# main_board.net
KiCad netlist of a schematic drawn in EAGLE
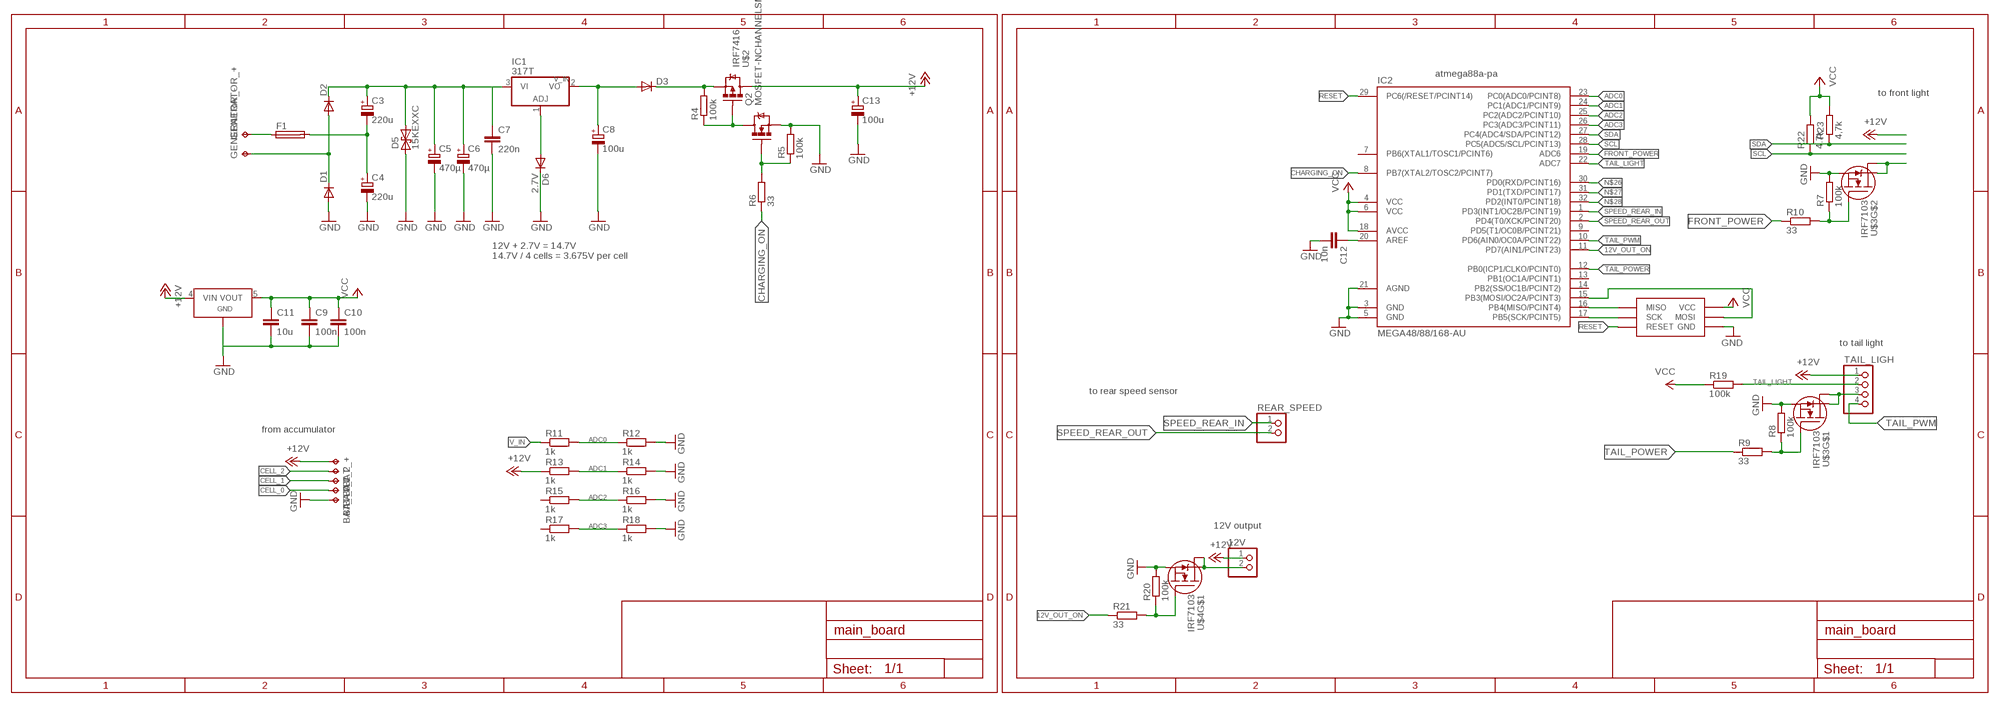
[diagram p0: schematic, sheet 1]

(export (version "E")
  (design (tool "Eeschema 10.0.6"))
  (components
    (comp (ref "12V")
      (value "PINHD-1X2")
      (footprint "eagle-import:1X02")
      (libsource (lib "eagle-import") (part "PINHD-1X2"))
    )
    (comp (ref "BAT_+")
      (value "TPTP18SQ")
      (footprint "eagle-import:TP18SQ")
      (libsource (lib "eagle-import") (part "TPTP18SQ"))
    )
    (comp (ref "BAT_-")
      (value "TPTP18SQ")
      (footprint "eagle-import:TP18SQ")
      (libsource (lib "eagle-import") (part "TPTP18SQ"))
    )
    (comp (ref "BAT_0")
      (value "TPTP18SQ")
      (footprint "eagle-import:TP18SQ")
      (libsource (lib "eagle-import") (part "TPTP18SQ"))
    )
    (comp (ref "BAT_1")
      (value "TPTP18SQ")
      (footprint "eagle-import:TP18SQ")
      (libsource (lib "eagle-import") (part "TPTP18SQ"))
    )
    (comp (ref "BAT_2")
      (value "TPTP18SQ")
      (footprint "eagle-import:TP18SQ")
      (libsource (lib "eagle-import") (part "TPTP18SQ"))
    )
    (comp (ref "C3")
      (value "220u")
      (footprint "eagle-import:PANASONIC_F")
      (libsource (lib "eagle-import") (part "CPOL-EUF"))
    )
    (comp (ref "C4")
      (value "220u")
      (footprint "eagle-import:PANASONIC_F")
      (libsource (lib "eagle-import") (part "CPOL-EUF"))
    )
    (comp (ref "C5")
      (value "470µ")
      (footprint "eagle-import:153CLV-1014")
      (libsource (lib "eagle-import") (part "CPOL-EU153CLV-1014"))
    )
    (comp (ref "C6")
      (value "470µ")
      (footprint "eagle-import:153CLV-1014")
      (libsource (lib "eagle-import") (part "CPOL-EU153CLV-1014"))
    )
    (comp (ref "C7")
      (value "220n")
      (footprint "eagle-import:C0805")
      (libsource (lib "eagle-import") (part "C-EUC0805"))
    )
    (comp (ref "C8")
      (value "100u")
      (footprint "eagle-import:PANASONIC_E")
      (libsource (lib "eagle-import") (part "CPOL-EUE"))
    )
    (comp (ref "C9")
      (value "100n")
      (footprint "eagle-import:C0805")
      (libsource (lib "eagle-import") (part "C-EUC0805"))
    )
    (comp (ref "C10")
      (value "100n")
      (footprint "eagle-import:C0805")
      (libsource (lib "eagle-import") (part "C-EUC0805"))
    )
    (comp (ref "C11")
      (value "10u")
      (footprint "eagle-import:C1206")
      (libsource (lib "eagle-import") (part "C-EUC1206"))
    )
    (comp (ref "C12")
      (value "10n")
      (footprint "eagle-import:C0805")
      (libsource (lib "eagle-import") (part "C-EUC0805"))
    )
    (comp (ref "C13")
      (value "100u")
      (footprint "eagle-import:PANASONIC_E")
      (libsource (lib "eagle-import") (part "CPOL-EUE"))
    )
    (comp (ref "D1")
      (value "DIODE-DO-214AC")
      (footprint "eagle-import:DO-214AC")
      (libsource (lib "eagle-import") (part "DIODE-DO-214AC"))
    )
    (comp (ref "D2")
      (value "DIODE-DO-214AC")
      (footprint "eagle-import:DO-214AC")
      (libsource (lib "eagle-import") (part "DIODE-DO-214AC"))
    )
    (comp (ref "D3")
      (value "DIODE-DO-214AC")
      (footprint "eagle-import:DO-214AC")
      (libsource (lib "eagle-import") (part "DIODE-DO-214AC"))
    )
    (comp (ref "D5")
      (value "15KEXXC")
      (footprint "eagle-import:CB429-17")
      (libsource (lib "eagle-import") (part "15KEXXC"))
    )
    (comp (ref "D6")
      (value "2.7V")
      (footprint "eagle-import:MINIMELF")
      (libsource (lib "eagle-import") (part "DIODE-MINIMELF"))
    )
    (comp (ref "F1")
      (value "TE5")
      (footprint "eagle-import:TE5")
      (fields (field (name "OC_FARNELL") "unknown") (field (name "OC_NEWARK") "unknown"))
      (libsource (lib "eagle-import") (part "TE5"))
    )
    (comp (ref "GENERATOR_+")
      (value "TPTP18SQ")
      (footprint "eagle-import:TP18SQ")
      (libsource (lib "eagle-import") (part "TPTP18SQ"))
    )
    (comp (ref "GENERATOR_-")
      (value "TPTP18SQ")
      (footprint "eagle-import:TP18SQ")
      (libsource (lib "eagle-import") (part "TPTP18SQ"))
    )
    (comp (ref "IC1")
      (value "317T")
      (footprint "eagle-import:TO220H")
      (libsource (lib "eagle-import") (part "317T"))
    )
    (comp (ref "IC2")
      (value "MEGA48/88/168-AU")
      (footprint "eagle-import:TQFP32-08")
      (libsource (lib "eagle-import") (part "MEGA48/88/168-AU"))
    )
    (comp (ref "Q2")
      (value "MOSFET-NCHANNELSMD")
      (footprint "eagle-import:SOT23-3")
      (libsource (lib "eagle-import") (part "MOSFET-NCHANNELSMD"))
    )
    (comp (ref "R4")
      (value "100k")
      (footprint "eagle-import:R0603")
      (libsource (lib "eagle-import") (part "R-EU_R0603"))
    )
    (comp (ref "R5")
      (value "100k")
      (footprint "eagle-import:R0603")
      (libsource (lib "eagle-import") (part "R-EU_R0603"))
    )
    (comp (ref "R6")
      (value "33")
      (footprint "eagle-import:R0603")
      (libsource (lib "eagle-import") (part "R-EU_R0603"))
    )
    (comp (ref "R7")
      (value "100k")
      (footprint "eagle-import:R0603")
      (libsource (lib "eagle-import") (part "R-EU_R0603"))
    )
    (comp (ref "R8")
      (value "100k")
      (footprint "eagle-import:R0603")
      (libsource (lib "eagle-import") (part "R-EU_R0603"))
    )
    (comp (ref "R9")
      (value "33")
      (footprint "eagle-import:R0603")
      (libsource (lib "eagle-import") (part "R-EU_R0603"))
    )
    (comp (ref "R10")
      (value "33")
      (footprint "eagle-import:R0603")
      (libsource (lib "eagle-import") (part "R-EU_R0603"))
    )
    (comp (ref "R11")
      (value "1k")
      (footprint "eagle-import:R0603")
      (libsource (lib "eagle-import") (part "R-EU_R0603"))
    )
    (comp (ref "R12")
      (value "1k")
      (footprint "eagle-import:R0603")
      (libsource (lib "eagle-import") (part "R-EU_R0603"))
    )
    (comp (ref "R13")
      (value "1k")
      (footprint "eagle-import:R0603")
      (libsource (lib "eagle-import") (part "R-EU_R0603"))
    )
    (comp (ref "R14")
      (value "1k")
      (footprint "eagle-import:R0603")
      (libsource (lib "eagle-import") (part "R-EU_R0603"))
    )
    (comp (ref "R15")
      (value "1k")
      (footprint "eagle-import:R0603")
      (libsource (lib "eagle-import") (part "R-EU_R0603"))
    )
    (comp (ref "R16")
      (value "1k")
      (footprint "eagle-import:R0603")
      (libsource (lib "eagle-import") (part "R-EU_R0603"))
    )
    (comp (ref "R17")
      (value "1k")
      (footprint "eagle-import:R0603")
      (libsource (lib "eagle-import") (part "R-EU_R0603"))
    )
    (comp (ref "R18")
      (value "1k")
      (footprint "eagle-import:R0603")
      (libsource (lib "eagle-import") (part "R-EU_R0603"))
    )
    (comp (ref "R19")
      (value "100k")
      (footprint "eagle-import:R0603")
      (libsource (lib "eagle-import") (part "R-EU_R0603"))
    )
    (comp (ref "R20")
      (value "100k")
      (footprint "eagle-import:R0603")
      (libsource (lib "eagle-import") (part "R-EU_R0603"))
    )
    (comp (ref "R21")
      (value "33")
      (footprint "eagle-import:R0603")
      (libsource (lib "eagle-import") (part "R-EU_R0603"))
    )
    (comp (ref "R22")
      (value "4.7k")
      (footprint "eagle-import:R0603")
      (libsource (lib "eagle-import") (part "R-EU_R0603"))
    )
    (comp (ref "R23")
      (value "4,7k")
      (footprint "eagle-import:R0603")
      (libsource (lib "eagle-import") (part "R-EU_R0603"))
    )
    (comp (ref "REAR_SPEED")
      (value "PINHD-1X2")
      (footprint "eagle-import:1X02")
      (libsource (lib "eagle-import") (part "PINHD-1X2"))
    )
    (comp (ref "TAIL_LIGH")
      (value "PINHD-1X4")
      (footprint "eagle-import:1X04")
      (libsource (lib "eagle-import") (part "PINHD-1X4"))
    )
    (comp (ref "U$1")
      (value "TPS71530")
      (footprint "eagle-import:SOT23-DBV")
      (libsource (lib "eagle-import") (part "TPS71530"))
    )
    (comp (ref "U$2")
      (value "IRF7416")
      (footprint "eagle-import:SO8-2")
      (libsource (lib "eagle-import") (part "IRF7416"))
    )
    (comp (ref "U$3")
      (value "IRF7103")
      (footprint "eagle-import:SO8-2")
      (libsource (lib "eagle-import") (part "IRF7103"))
    )
    (comp (ref "U$4")
      (value "IRF7103")
      (footprint "eagle-import:SO8-2")
      (libsource (lib "eagle-import") (part "IRF7103"))
    )
    (comp (ref "U$5")
      (value "ISP_SPECIALS")
      (footprint "eagle-import:ISP_RM2_00_STRAIGHT")
      (libsource (lib "eagle-import") (part "ISP_SPECIALS"))
    )
  )
  (nets
    (net (code "1") (name "+12V") (class "Default")
      (node (ref "12V") (pin "1") (pinfunction "1_1") (pintype "passive"))
      (node (ref "BAT_+") (pin "TP") (pinfunction "TP_TP") (pintype "input"))
      (node (ref "C13") (pin "+") (pinfunction "+_+") (pintype "passive"))
      (node (ref "R13") (pin "1") (pinfunction "1_1") (pintype "passive"))
      (node (ref "TAIL_LIGH") (pin "1") (pinfunction "1_1") (pintype "passive"))
      (node (ref "U$1") (pin "4") (pinfunction "VIN_4") (pintype "power_in"))
      (node (ref "U$2") (pin "5") (pinfunction "D1_5") (pintype "passive"))
      (node (ref "U$2") (pin "6") (pinfunction "D1_6") (pintype "passive"))
      (node (ref "U$2") (pin "7") (pinfunction "D1_7") (pintype "passive"))
      (node (ref "U$2") (pin "8") (pinfunction "D1_8") (pintype "passive"))
    )
    (net (code "2") (name "12V_OUT_ON") (class "Default")
      (node (ref "IC2") (pin "11") (pinfunction "PD7(AIN1/PCINT23)_11") (pintype "bidirectional"))
      (node (ref "R21") (pin "1") (pinfunction "1_1") (pintype "passive"))
    )
    (net (code "3") (name "ADC0") (class "Default")
      (node (ref "IC2") (pin "23") (pinfunction "PC0(ADC0/PCINT8)_23") (pintype "bidirectional"))
      (node (ref "R11") (pin "2") (pinfunction "2_2") (pintype "passive"))
      (node (ref "R12") (pin "1") (pinfunction "1_1") (pintype "passive"))
    )
    (net (code "4") (name "ADC1") (class "Default")
      (node (ref "IC2") (pin "24") (pinfunction "PC1(ADC1/PCINT9)_24") (pintype "bidirectional"))
      (node (ref "R13") (pin "2") (pinfunction "2_2") (pintype "passive"))
      (node (ref "R14") (pin "1") (pinfunction "1_1") (pintype "passive"))
    )
    (net (code "5") (name "ADC2") (class "Default")
      (node (ref "IC2") (pin "25") (pinfunction "PC2(ADC2/PCINT10)_25") (pintype "bidirectional"))
      (node (ref "R15") (pin "2") (pinfunction "2_2") (pintype "passive"))
      (node (ref "R16") (pin "1") (pinfunction "1_1") (pintype "passive"))
    )
    (net (code "6") (name "ADC3") (class "Default")
      (node (ref "IC2") (pin "26") (pinfunction "PC3(ADC3/PCINT11)_26") (pintype "bidirectional"))
      (node (ref "R17") (pin "2") (pinfunction "2_2") (pintype "passive"))
      (node (ref "R18") (pin "1") (pinfunction "1_1") (pintype "passive"))
    )
    (net (code "7") (name "CELL_0") (class "Default")
      (node (ref "BAT_0") (pin "TP") (pinfunction "TP_TP") (pintype "input"))
    )
    (net (code "8") (name "CELL_1") (class "Default")
      (node (ref "BAT_1") (pin "TP") (pinfunction "TP_TP") (pintype "input"))
    )
    (net (code "9") (name "CELL_2") (class "Default")
      (node (ref "BAT_2") (pin "TP") (pinfunction "TP_TP") (pintype "input"))
    )
    (net (code "10") (name "CHARGING_ON") (class "Default")
      (node (ref "IC2") (pin "8") (pinfunction "PB7(XTAL2/TOSC2/PCINT7)_8") (pintype "bidirectional"))
      (node (ref "R6") (pin "1") (pinfunction "1_1") (pintype "passive"))
    )
    (net (code "11") (name "FRONT_POWER") (class "Default")
      (node (ref "IC2") (pin "19") (pinfunction "ADC6_19") (pintype "passive"))
      (node (ref "R10") (pin "1") (pinfunction "1_1") (pintype "passive"))
    )
    (net (code "12") (name "GND") (class "Default")
      (node (ref "BAT_-") (pin "TP") (pinfunction "TP_TP") (pintype "input"))
      (node (ref "C10") (pin "2") (pinfunction "2_2") (pintype "passive"))
      (node (ref "C11") (pin "2") (pinfunction "2_2") (pintype "passive"))
      (node (ref "C12") (pin "2") (pinfunction "2_2") (pintype "passive"))
      (node (ref "C13") (pin "-") (pinfunction "-_-") (pintype "passive"))
      (node (ref "C4") (pin "-") (pinfunction "-_-") (pintype "passive"))
      (node (ref "C5") (pin "-") (pinfunction "-_-") (pintype "passive"))
      (node (ref "C6") (pin "-") (pinfunction "-_-") (pintype "passive"))
      (node (ref "C7") (pin "2") (pinfunction "2_2") (pintype "passive"))
      (node (ref "C8") (pin "-") (pinfunction "-_-") (pintype "passive"))
      (node (ref "C9") (pin "2") (pinfunction "2_2") (pintype "passive"))
      (node (ref "D1") (pin "A") (pinfunction "A_A") (pintype "passive"))
      (node (ref "D5") (pin "A") (pinfunction "1_A") (pintype "passive"))
      (node (ref "D6") (pin "C") (pinfunction "C_C") (pintype "passive"))
      (node (ref "IC2") (pin "21") (pinfunction "AGND_21") (pintype "power_in"))
      (node (ref "IC2") (pin "3") (pinfunction "GND_3") (pintype "power_in"))
      (node (ref "IC2") (pin "5") (pinfunction "GND_5") (pintype "power_in"))
      (node (ref "Q2") (pin "2") (pinfunction "S_2") (pintype "passive"))
      (node (ref "R12") (pin "2") (pinfunction "2_2") (pintype "passive"))
      (node (ref "R14") (pin "2") (pinfunction "2_2") (pintype "passive"))
      (node (ref "R16") (pin "2") (pinfunction "2_2") (pintype "passive"))
      (node (ref "R18") (pin "2") (pinfunction "2_2") (pintype "passive"))
      (node (ref "R20") (pin "2") (pinfunction "2_2") (pintype "passive"))
      (node (ref "R5") (pin "2") (pinfunction "2_2") (pintype "passive"))
      (node (ref "R7") (pin "2") (pinfunction "2_2") (pintype "passive"))
      (node (ref "R8") (pin "2") (pinfunction "2_2") (pintype "passive"))
      (node (ref "U$1") (pin "2") (pinfunction "GND_2") (pintype "power_in"))
      (node (ref "U$3") (pin "1") (pinfunction "S_1") (pintype "bidirectional"))
      (node (ref "U$3") (pin "3") (pinfunction "S_3") (pintype "bidirectional"))
      (node (ref "U$4") (pin "1") (pinfunction "S_1") (pintype "bidirectional"))
      (node (ref "U$5") (pin "VCC") (pinfunction "GND_VCC") (pintype "bidirectional"))
    )
    (net (code "13") (name "N$26") (class "Default")
      (node (ref "IC2") (pin "30") (pinfunction "PD0(RXD/PCINT16)_30") (pintype "bidirectional"))
    )
    (net (code "14") (name "N$27") (class "Default")
      (node (ref "IC2") (pin "31") (pinfunction "PD1(TXD/PCINT17)_31") (pintype "bidirectional"))
    )
    (net (code "15") (name "N$28") (class "Default")
      (node (ref "IC2") (pin "32") (pinfunction "PD2(INT0/PCINT18)_32") (pintype "bidirectional"))
    )
    (net (code "16") (name "Net-(12V-Pad2)") (class "Default")
      (node (ref "12V") (pin "2") (pinfunction "2_2") (pintype "passive"))
      (node (ref "U$4") (pin "7") (pinfunction "D_7") (pintype "bidirectional"))
      (node (ref "U$4") (pin "8") (pinfunction "D_8") (pintype "bidirectional"))
    )
    (net (code "17") (name "Net-(C3-Pad-)") (class "Default")
      (node (ref "C3") (pin "-") (pinfunction "-_-") (pintype "passive"))
      (node (ref "C4") (pin "+") (pinfunction "+_+") (pintype "passive"))
      (node (ref "F1") (pin "2") (pinfunction "2_2") (pintype "passive"))
    )
    (net (code "18") (name "Net-(D1-PadC)") (class "Default")
      (node (ref "D1") (pin "C") (pinfunction "C_C") (pintype "passive"))
      (node (ref "D2") (pin "A") (pinfunction "A_A") (pintype "passive"))
      (node (ref "GENERATOR_-") (pin "TP") (pinfunction "TP_TP") (pintype "input"))
    )
    (net (code "19") (name "Net-(D3-PadC)") (class "Default")
      (node (ref "D3") (pin "C") (pinfunction "C_C") (pintype "passive"))
      (node (ref "R4") (pin "2") (pinfunction "2_2") (pintype "passive"))
      (node (ref "U$2") (pin "1") (pinfunction "S1_1") (pintype "passive"))
      (node (ref "U$2") (pin "2") (pinfunction "S1_2") (pintype "passive"))
      (node (ref "U$2") (pin "3") (pinfunction "S1_3") (pintype "passive"))
    )
    (net (code "20") (name "Net-(F1-Pad1)") (class "Default")
      (node (ref "F1") (pin "1") (pinfunction "1_1") (pintype "passive"))
      (node (ref "GENERATOR_+") (pin "TP") (pinfunction "TP_TP") (pintype "input"))
    )
    (net (code "21") (name "Net-(IC1-ADJ)") (class "Default")
      (node (ref "D6") (pin "A") (pinfunction "A_A") (pintype "passive"))
      (node (ref "IC1") (pin "1") (pinfunction "ADJ_1") (pintype "input"))
    )
    (net (code "22") (name "Net-(IC1-VO)") (class "Default")
      (node (ref "C8") (pin "+") (pinfunction "+_+") (pintype "passive"))
      (node (ref "D3") (pin "A") (pinfunction "A_A") (pintype "passive"))
      (node (ref "IC1") (pin "2") (pinfunction "VO_2") (pintype "passive"))
    )
    (net (code "23") (name "Net-(IC2-AREF)") (class "Default")
      (node (ref "C12") (pin "1") (pinfunction "1_1") (pintype "passive"))
      (node (ref "IC2") (pin "20") (pinfunction "AREF_20") (pintype "passive"))
    )
    (net (code "24") (name "Net-(IC2-PB3(MOSI{slash}OC2A{slash}PCINT3))") (class "Default")
      (node (ref "IC2") (pin "15") (pinfunction "PB3(MOSI/OC2A/PCINT3)_15") (pintype "bidirectional"))
      (node (ref "U$5") (pin "MOSI") (pinfunction "MOSI_MOSI") (pintype "bidirectional"))
    )
    (net (code "25") (name "Net-(IC2-PB4(MISO{slash}PCINT4))") (class "Default")
      (node (ref "IC2") (pin "16") (pinfunction "PB4(MISO/PCINT4)_16") (pintype "bidirectional"))
      (node (ref "U$5") (pin "RESET") (pinfunction "MISO_RESET") (pintype "bidirectional"))
    )
    (net (code "26") (name "Net-(IC2-PB5(SCK{slash}PCINT5))") (class "Default")
      (node (ref "IC2") (pin "17") (pinfunction "PB5(SCK/PCINT5)_17") (pintype "bidirectional"))
      (node (ref "U$5") (pin "SCK") (pinfunction "SCK_SCK") (pintype "bidirectional"))
    )
    (net (code "27") (name "Net-(Q2-D)") (class "Default")
      (node (ref "Q2") (pin "3") (pinfunction "D_3") (pintype "passive"))
      (node (ref "R4") (pin "1") (pinfunction "1_1") (pintype "passive"))
      (node (ref "U$2") (pin "4") (pinfunction "G_4") (pintype "passive"))
    )
    (net (code "28") (name "Net-(Q2-G)") (class "Default")
      (node (ref "Q2") (pin "1") (pinfunction "G_1") (pintype "passive"))
      (node (ref "R5") (pin "1") (pinfunction "1_1") (pintype "passive"))
      (node (ref "R6") (pin "2") (pinfunction "2_2") (pintype "passive"))
    )
    (net (code "29") (name "Net-(TAIL_LIGH-Pad3)") (class "Default")
      (node (ref "TAIL_LIGH") (pin "3") (pinfunction "3_3") (pintype "passive"))
      (node (ref "U$3") (pin "7") (pinfunction "D_7") (pintype "bidirectional"))
      (node (ref "U$3") (pin "8") (pinfunction "D_8") (pintype "bidirectional"))
    )
    (net (code "30") (name "Net-(U$3A-G)") (class "Default")
      (node (ref "R8") (pin "1") (pinfunction "1_1") (pintype "passive"))
      (node (ref "R9") (pin "2") (pinfunction "2_2") (pintype "passive"))
      (node (ref "U$3") (pin "2") (pinfunction "G_2") (pintype "bidirectional"))
    )
    (net (code "31") (name "Net-(U$3B-D-Pad5)") (class "Default")
      (node (ref "U$3") (pin "5") (pinfunction "D_5") (pintype "bidirectional"))
      (node (ref "U$3") (pin "6") (pinfunction "D_6") (pintype "bidirectional"))
    )
    (net (code "32") (name "Net-(U$3B-G)") (class "Default")
      (node (ref "R10") (pin "2") (pinfunction "2_2") (pintype "passive"))
      (node (ref "R7") (pin "1") (pinfunction "1_1") (pintype "passive"))
      (node (ref "U$3") (pin "4") (pinfunction "G_4") (pintype "bidirectional"))
    )
    (net (code "33") (name "Net-(U$4A-G)") (class "Default")
      (node (ref "R20") (pin "1") (pinfunction "1_1") (pintype "passive"))
      (node (ref "R21") (pin "2") (pinfunction "2_2") (pintype "passive"))
      (node (ref "U$4") (pin "2") (pinfunction "G_2") (pintype "bidirectional"))
    )
    (net (code "34") (name "RESET") (class "Default")
      (node (ref "IC2") (pin "29") (pinfunction "PC6(/RESET/PCINT14)_29") (pintype "bidirectional"))
      (node (ref "U$5") (pin "MISO") (pinfunction "RESET_MISO") (pintype "bidirectional"))
    )
    (net (code "35") (name "SCL") (class "Default")
      (node (ref "IC2") (pin "28") (pinfunction "PC5(ADC5/SCL/PCINT13)_28") (pintype "bidirectional"))
      (node (ref "R22") (pin "1") (pinfunction "1_1") (pintype "passive"))
    )
    (net (code "36") (name "SDA") (class "Default")
      (node (ref "IC2") (pin "27") (pinfunction "PC4(ADC4/SDA/PCINT12)_27") (pintype "bidirectional"))
      (node (ref "R23") (pin "1") (pinfunction "1_1") (pintype "passive"))
    )
    (net (code "37") (name "SPEED_REAR_IN") (class "Default")
      (node (ref "IC2") (pin "1") (pinfunction "PD3(INT1/OC2B/PCINT19)_1") (pintype "bidirectional"))
      (node (ref "REAR_SPEED") (pin "1") (pinfunction "1_1") (pintype "passive"))
    )
    (net (code "38") (name "SPEED_REAR_OUT") (class "Default")
      (node (ref "IC2") (pin "2") (pinfunction "PD4(T0/XCK/PCINT20)_2") (pintype "bidirectional"))
      (node (ref "REAR_SPEED") (pin "2") (pinfunction "2_2") (pintype "passive"))
    )
    (net (code "39") (name "TAIL_LIGHT") (class "Default")
      (node (ref "IC2") (pin "22") (pinfunction "ADC7_22") (pintype "passive"))
      (node (ref "R19") (pin "2") (pinfunction "2_2") (pintype "passive"))
      (node (ref "TAIL_LIGH") (pin "2") (pinfunction "2_2") (pintype "passive"))
    )
    (net (code "40") (name "TAIL_POWER") (class "Default")
      (node (ref "IC2") (pin "12") (pinfunction "PB0(ICP1/CLKO/PCINT0)_12") (pintype "bidirectional"))
      (node (ref "R9") (pin "1") (pinfunction "1_1") (pintype "passive"))
    )
    (net (code "41") (name "TAIL_PWM") (class "Default")
      (node (ref "IC2") (pin "10") (pinfunction "PD6(AIN0/OC0A/PCINT22)_10") (pintype "bidirectional"))
      (node (ref "TAIL_LIGH") (pin "4") (pinfunction "4_4") (pintype "passive"))
    )
    (net (code "42") (name "VCC") (class "Default")
      (node (ref "C10") (pin "1") (pinfunction "1_1") (pintype "passive"))
      (node (ref "C11") (pin "1") (pinfunction "1_1") (pintype "passive"))
      (node (ref "C9") (pin "1") (pinfunction "1_1") (pintype "passive"))
      (node (ref "IC2") (pin "18") (pinfunction "AVCC_18") (pintype "passive"))
      (node (ref "IC2") (pin "4") (pinfunction "VCC_4") (pintype "power_in"))
      (node (ref "IC2") (pin "6") (pinfunction "VCC_6") (pintype "power_in"))
      (node (ref "R19") (pin "1") (pinfunction "1_1") (pintype "passive"))
      (node (ref "R22") (pin "2") (pinfunction "2_2") (pintype "passive"))
      (node (ref "R23") (pin "2") (pinfunction "2_2") (pintype "passive"))
      (node (ref "U$1") (pin "5") (pinfunction "VOUT_5") (pintype "power_in"))
      (node (ref "U$5") (pin "GND") (pinfunction "VCC_GND") (pintype "bidirectional"))
    )
    (net (code "43") (name "V_IN") (class "Default")
      (node (ref "C3") (pin "+") (pinfunction "+_+") (pintype "passive"))
      (node (ref "C5") (pin "+") (pinfunction "+_+") (pintype "passive"))
      (node (ref "C6") (pin "+") (pinfunction "+_+") (pintype "passive"))
      (node (ref "C7") (pin "1") (pinfunction "1_1") (pintype "passive"))
      (node (ref "D2") (pin "C") (pinfunction "C_C") (pintype "passive"))
      (node (ref "D5") (pin "C") (pinfunction "2_C") (pintype "passive"))
      (node (ref "IC1") (pin "3") (pinfunction "VI_3") (pintype "input"))
      (node (ref "R11") (pin "1") (pinfunction "1_1") (pintype "passive"))
    )
    (net (code "44") (name "unconnected-(IC2-PB1(OC1A{slash}PCINT1)-Pad13)") (class "Default")
      (node (ref "IC2") (pin "13") (pinfunction "PB1(OC1A/PCINT1)_13") (pintype "bidirectional"))
    )
    (net (code "45") (name "unconnected-(IC2-PB2(SS{slash}OC1B{slash}PCINT2)-Pad14)") (class "Default")
      (node (ref "IC2") (pin "14") (pinfunction "PB2(SS/OC1B/PCINT2)_14") (pintype "bidirectional"))
    )
    (net (code "46") (name "unconnected-(IC2-PB6(XTAL1{slash}TOSC1{slash}PCINT6)-Pad7)") (class "Default")
      (node (ref "IC2") (pin "7") (pinfunction "PB6(XTAL1/TOSC1/PCINT6)_7") (pintype "bidirectional"))
    )
    (net (code "47") (name "unconnected-(IC2-PD5(T1{slash}OC0B{slash}PCINT21)-Pad9)") (class "Default")
      (node (ref "IC2") (pin "9") (pinfunction "PD5(T1/OC0B/PCINT21)_9") (pintype "bidirectional"))
    )
    (net (code "48") (name "unconnected-(R15-Pad1)") (class "Default")
      (node (ref "R15") (pin "1") (pinfunction "1_1") (pintype "passive"))
    )
    (net (code "49") (name "unconnected-(R17-Pad1)") (class "Default")
      (node (ref "R17") (pin "1") (pinfunction "1_1") (pintype "passive"))
    )
  )
)
